# Power_24Vto160V.net
KiCad netlist of a schematic drawn in Altium Designer
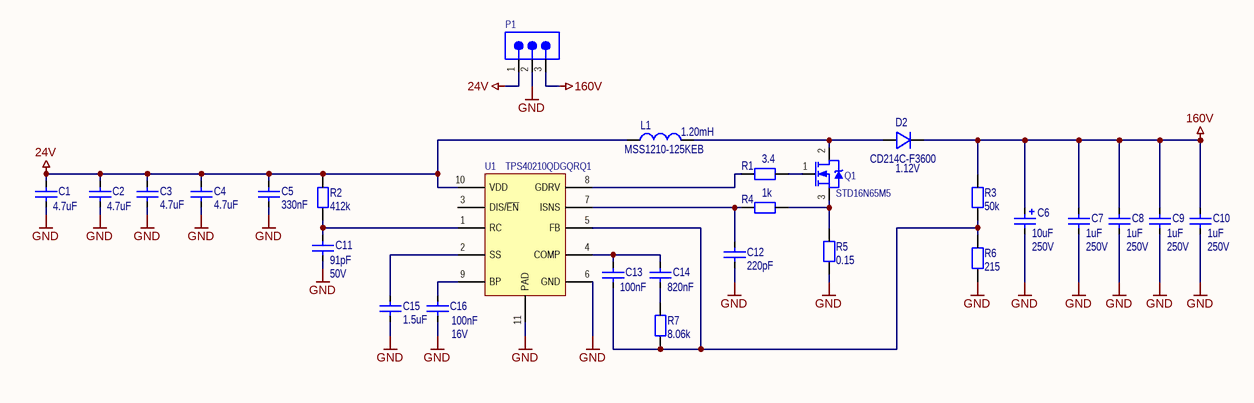
[diagram p0: Power_24Vto160V.SchDoc]

(export (version "E")
  (design (tool "Eeschema 10.0.6"))
  (components
    (comp (ref "C1")
      (value "4.7uF")
      (footprint "1210_C")
      (description "GRM32ER71H475KA88L")
      (fields (field (name "TOLERANCE") "±10%") (field (name "MANUFACTURER") "muRata"))
      (libsource (lib "Nixie") (part "GRM32ER71H475KA88L"))
    )
    (comp (ref "C2")
      (value "4.7uF")
      (footprint "1210_C")
      (description "GRM32ER71H475KA88L")
      (fields (field (name "TOLERANCE") "±10%") (field (name "MANUFACTURER") "muRata"))
      (libsource (lib "Nixie") (part "GRM32ER71H475KA88L"))
    )
    (comp (ref "C3")
      (value "4.7uF")
      (footprint "1210_C")
      (description "GRM32ER71H475KA88L")
      (fields (field (name "TOLERANCE") "±10%") (field (name "MANUFACTURER") "muRata"))
      (libsource (lib "Nixie") (part "GRM32ER71H475KA88L"))
    )
    (comp (ref "C4")
      (value "4.7uF")
      (footprint "1210_C")
      (description "GRM32ER71H475KA88L")
      (fields (field (name "TOLERANCE") "±10%") (field (name "MANUFACTURER") "muRata"))
      (libsource (lib "Nixie") (part "GRM32ER71H475KA88L"))
    )
    (comp (ref "C5")
      (value "330nF")
      (footprint "0603_C")
      (description "C1608X5R1H334K080AB")
      (fields (field (name "TOLERANCE") "±10%") (field (name "MANUFACTURER") "TDK"))
      (libsource (lib "Nixie") (part "C1608X5R1H334K080AB"))
    )
    (comp (ref "C6")
      (value "10uF")
      (footprint "CAPAE109103X100M")
      (description "UUX2E100MNL1GS")
      (fields
        (field (name "TOLERANCE") "±20%")
        (field (name "MANUFACTURER") "Nichicon")
        (field (name "VOLTAGE_RATING") "250V")
      )
      (libsource (lib "Nixie") (part "UUX2E100MNL1GS"))
    )
    (comp (ref "C7")
      (value "1uF")
      (footprint "CAPC5750X27_EIA-2220")
      (description "GRM55DR72E105KW01L")
      (fields
        (field (name "TOLERANCE") "±10%")
        (field (name "VOLTAGE_RATING") "250V")
        (field (name "MANUFACTURER") "muRata")
      )
      (libsource (lib "Nixie") (part "GRM55DR72E105KW01L"))
    )
    (comp (ref "C8")
      (value "1uF")
      (footprint "CAPC5750X27_EIA-2220")
      (description "GRM55DR72E105KW01L")
      (fields
        (field (name "TOLERANCE") "±10%")
        (field (name "VOLTAGE_RATING") "250V")
        (field (name "MANUFACTURER") "muRata")
      )
      (libsource (lib "Nixie") (part "GRM55DR72E105KW01L"))
    )
    (comp (ref "C9")
      (value "1uF")
      (footprint "CAPC5750X27_EIA-2220")
      (description "GRM55DR72E105KW01L")
      (fields
        (field (name "TOLERANCE") "±10%")
        (field (name "VOLTAGE_RATING") "250V")
        (field (name "MANUFACTURER") "muRata")
      )
      (libsource (lib "Nixie") (part "GRM55DR72E105KW01L"))
    )
    (comp (ref "C10")
      (value "1uF")
      (footprint "CAPC5750X27_EIA-2220")
      (description "GRM55DR72E105KW01L")
      (fields
        (field (name "TOLERANCE") "±10%")
        (field (name "VOLTAGE_RATING") "250V")
        (field (name "MANUFACTURER") "muRata")
      )
      (libsource (lib "Nixie") (part "GRM55DR72E105KW01L"))
    )
    (comp (ref "C11")
      (value "91pF")
      (footprint "0603_C")
      (description "GRM1885C1H910JA01D")
      (fields
        (field (name "TOLERANCE") "±10%")
        (field (name "VOLTAGE_RATING") "50V")
        (field (name "MANUFACTURER") "muRata")
      )
      (libsource (lib "Nixie") (part "GRM1885C1H910JA01D"))
    )
    (comp (ref "C12")
      (value "220pF")
      (footprint "CAPC2012X12_EIA-0805")
      (description "CC0805JRNPO9BN221")
      (fields (field (name "TOLERANCE") "±10%") (field (name "MANUFACTURER") "Yageo"))
      (libsource (lib "Nixie") (part "CC0805JRNPO9BN221"))
    )
    (comp (ref "C13")
      (value "100nF")
      (footprint "CAPC2012X12_EIA-0805")
      (description "CC0805KRX7R8BB104")
      (fields (field (name "TOLERANCE") "±10%") (field (name "MANUFACTURER") "Yageo"))
      (libsource (lib "Nixie") (part "CC0805KRX7R8BB104"))
    )
    (comp (ref "C14")
      (value "820nF")
      (footprint "CAPC1005X05_EIA-0402")
      (description "GRM155R61A824KE15D")
      (fields (field (name "TOLERANCE") "±10%") (field (name "MANUFACTURER") "muRata"))
      (libsource (lib "Nixie") (part "GRM155R61A824KE15D"))
    )
    (comp (ref "C15")
      (value "1.5uF")
      (footprint "0603_C")
      (description "C1608X7R1A155K080AC")
      (fields (field (name "TOLERANCE") "±10%") (field (name "MANUFACTURER") "TDK"))
      (libsource (lib "Nixie") (part "C1608X7R1A155K080AC"))
    )
    (comp (ref "C16")
      (value "100nF")
      (footprint "0603_C")
      (description "EMK107B7105KA-T")
      (fields
        (field (name "TOLERANCE") "±10%")
        (field (name "VOLTAGE_RATING") "16V")
        (field (name "MANUFACTURER") "Taiyo Yuden")
      )
      (libsource (lib "Nixie") (part "EMK107B7105KA-T"))
    )
    (comp (ref "D2")
      (value "CD214C-F3600")
      (footprint "DIOM6959X26N")
      (description "600V, 3amp")
      (fields (field (name "VOLTAGE") "1.12V"))
      (libsource (lib "Nixie") (part "CD214C-F3600"))
    )
    (comp (ref "L1")
      (value "1.20mH")
      (footprint "IND_COILCRAFT_MSS1260")
      (description "Inductor")
      (fields (field (name "ORDERNUMBER") "MSS1210-125KEB"))
      (libsource (lib "Nixie") (part "MSS1210-125KEB"))
    )
    (comp (ref "P1")
      (value "power")
      (footprint "MOLEX_22-28-4030")
      (description "Header single row 1x3pin")
      (fields
        (field (name "PART_NUMBER") "1007795")
        (field (name "MANUFACTURER") "molex")
        (field (name "CHECK_STATE") "2014-07-24_DW_MJ")
      )
      (libsource (lib "PCB") (part "M_1x3PIN-molex"))
    )
    (comp (ref "Q1")
      (value "STD16N65M5")
      (footprint "DPAK228P972X240-3N")
      (description "N-channel MOSFET 650V")
      (fields (field (name "ORDER_NUMBER") "STD16N65M5"))
      (libsource (lib "Nixie") (part "STD16N65M5"))
    )
    (comp (ref "R1")
      (value "3.4")
      (footprint "0603_R")
      (description "CRCW06033R40FKEA")
      (fields (field (name "PART_NUMBER") "1347890") (field (name "TOLERANCE") "1%"))
      (libsource (lib "Nixie") (part "CRCW06033R40FKEA"))
    )
    (comp (ref "R2")
      (value "412k")
      (footprint "0603_R")
      (description "ERJ-3EKF4123V")
      (fields (field (name "PART_NUMBER") "1347890") (field (name "TOLERANCE") "1%"))
      (libsource (lib "Nixie") (part "R_ERJ-3EKF4123V"))
    )
    (comp (ref "R3")
      (value "50k")
      (footprint "RESC3216X06_EIA-1206")
      (description "PNM1206E5002BST1")
      (fields (field (name "PART_NUMBER") "1347890") (field (name "TOLERANCE") "0.1%"))
      (libsource (lib "Nixie") (part "PNM1206E5002BST1"))
    )
    (comp (ref "R4")
      (value "1k")
      (footprint "0603_R")
      (description "CRCW02011K00FKED")
      (fields (field (name "PART_NUMBER") "1347890") (field (name "TOLERANCE") "1%"))
      (libsource (lib "Nixie") (part "CRCW02011K00FKED"))
    )
    (comp (ref "R5")
      (value "0.15")
      (footprint "0603_R")
      (description "ERJ-3RSFR15V")
      (fields (field (name "TOLERANCE") "1%") (field (name "MANUFACTURER") "Panasonic"))
      (libsource (lib "Nixie") (part "ERJ-3RSFR15V"))
    )
    (comp (ref "R6")
      (value "215")
      (footprint "0603_R")
      (description "ERJ-3EKF2150V")
      (fields (field (name "TOLERANCE") "1%") (field (name "MANUFACTURER") "Panasonic"))
      (libsource (lib "Nixie") (part "ERJ-3EKF2150V"))
    )
    (comp (ref "R7")
      (value "8.06k")
      (footprint "0603_R")
      (description "CRCW06038K06FKEA")
      (fields (field (name "PART_NUMBER") "1347890") (field (name "TOLERANCE") "1%"))
      (libsource (lib "Nixie") (part "R_CRCW06038K06FKEA"))
    )
    (comp (ref "U1")
      (value "TPS40210QDGQRQ1")
      (footprint "TSSOP50P490X110_HS-11N")
      (fields (field (name "MANUFACTURER") "TI") (field (name "ORDER_NUMBER") "TPS40210QDGQRQ1"))
      (libsource (lib "Nixie") (part "TPS40210-Q1"))
    )
  )
  (nets
    (net (code "1") (name "24V") (class "Default")
      (node (ref "C1") (pin "2") (pinfunction "2_2") (pintype "passive"))
      (node (ref "C2") (pin "2") (pinfunction "2_2") (pintype "passive"))
      (node (ref "C3") (pin "2") (pinfunction "2_2") (pintype "passive"))
      (node (ref "C4") (pin "2") (pinfunction "2_2") (pintype "passive"))
      (node (ref "C5") (pin "2") (pinfunction "2_2") (pintype "passive"))
      (node (ref "L1") (pin "1") (pinfunction "1_1") (pintype "passive"))
      (node (ref "P1") (pin "1") (pinfunction "1_1") (pintype "passive"))
      (node (ref "R2") (pin "2") (pinfunction "2_2") (pintype "passive"))
      (node (ref "U1") (pin "10") (pinfunction "VDD_10") (pintype "power_in"))
    )
    (net (code "2") (name "160V") (class "Default")
      (node (ref "C10") (pin "2") (pinfunction "2_2") (pintype "passive"))
      (node (ref "C6") (pin "1") (pinfunction "1_1") (pintype "passive"))
      (node (ref "C7") (pin "2") (pinfunction "2_2") (pintype "passive"))
      (node (ref "C8") (pin "2") (pinfunction "2_2") (pintype "passive"))
      (node (ref "C9") (pin "2") (pinfunction "2_2") (pintype "passive"))
      (node (ref "D2") (pin "1") (pinfunction "K_1") (pintype "passive"))
      (node (ref "P1") (pin "3") (pinfunction "3_3") (pintype "passive"))
      (node (ref "R3") (pin "2") (pinfunction "2_2") (pintype "passive"))
    )
    (net (code "3") (name "GND") (class "Default")
      (node (ref "C1") (pin "1") (pinfunction "1_1") (pintype "passive"))
      (node (ref "C10") (pin "1") (pinfunction "1_1") (pintype "passive"))
      (node (ref "C11") (pin "1") (pinfunction "1_1") (pintype "passive"))
      (node (ref "C12") (pin "1") (pinfunction "1_1") (pintype "passive"))
      (node (ref "C15") (pin "1") (pinfunction "1_1") (pintype "passive"))
      (node (ref "C16") (pin "1") (pinfunction "1_1") (pintype "passive"))
      (node (ref "C2") (pin "1") (pinfunction "1_1") (pintype "passive"))
      (node (ref "C3") (pin "1") (pinfunction "1_1") (pintype "passive"))
      (node (ref "C4") (pin "1") (pinfunction "1_1") (pintype "passive"))
      (node (ref "C5") (pin "1") (pinfunction "1_1") (pintype "passive"))
      (node (ref "C6") (pin "2") (pinfunction "2_2") (pintype "passive"))
      (node (ref "C7") (pin "1") (pinfunction "1_1") (pintype "passive"))
      (node (ref "C8") (pin "1") (pinfunction "1_1") (pintype "passive"))
      (node (ref "C9") (pin "1") (pinfunction "1_1") (pintype "passive"))
      (node (ref "P1") (pin "2") (pinfunction "2_2") (pintype "passive"))
      (node (ref "R5") (pin "1") (pinfunction "1_1") (pintype "passive"))
      (node (ref "R6") (pin "1") (pinfunction "1_1") (pintype "passive"))
      (node (ref "U1") (pin "11") (pinfunction "PAD_11") (pintype "power_in"))
      (node (ref "U1") (pin "6") (pinfunction "GND_6") (pintype "power_in"))
    )
    (net (code "4") (name "Net-(C14-Pad1)") (class "Default")
      (node (ref "C14") (pin "1") (pinfunction "1_1") (pintype "passive"))
      (node (ref "R7") (pin "2") (pinfunction "2_2") (pintype "passive"))
    )
    (net (code "5") (name "Net-(D2-A)") (class "Default")
      (node (ref "D2") (pin "2") (pinfunction "A_2") (pintype "passive"))
      (node (ref "L1") (pin "2") (pinfunction "2_2") (pintype "passive"))
      (node (ref "Q1") (pin "2") (pinfunction "D_2") (pintype "passive"))
    )
    (net (code "6") (name "Net-(Q1-G)") (class "Default")
      (node (ref "Q1") (pin "1") (pinfunction "G_1") (pintype "passive"))
      (node (ref "R1") (pin "2") (pinfunction "2_2") (pintype "passive"))
    )
    (net (code "7") (name "Net-(Q1-S)") (class "Default")
      (node (ref "Q1") (pin "3") (pinfunction "S_3") (pintype "passive"))
      (node (ref "R4") (pin "2") (pinfunction "2_2") (pintype "passive"))
      (node (ref "R5") (pin "2") (pinfunction "2_2") (pintype "passive"))
    )
    (net (code "8") (name "Net-(U1-BP)") (class "Default")
      (node (ref "C16") (pin "2") (pinfunction "2_2") (pintype "passive"))
      (node (ref "U1") (pin "9") (pinfunction "BP_9") (pintype "power_in"))
    )
    (net (code "9") (name "Net-(U1-COMP)") (class "Default")
      (node (ref "C13") (pin "2") (pinfunction "2_2") (pintype "passive"))
      (node (ref "C14") (pin "2") (pinfunction "2_2") (pintype "passive"))
      (node (ref "U1") (pin "4") (pinfunction "COMP_4") (pintype "power_in"))
    )
    (net (code "10") (name "Net-(U1-FB)") (class "Default")
      (node (ref "C13") (pin "1") (pinfunction "1_1") (pintype "passive"))
      (node (ref "R3") (pin "1") (pinfunction "1_1") (pintype "passive"))
      (node (ref "R6") (pin "2") (pinfunction "2_2") (pintype "passive"))
      (node (ref "R7") (pin "1") (pinfunction "1_1") (pintype "passive"))
      (node (ref "U1") (pin "5") (pinfunction "FB_5") (pintype "power_in"))
    )
    (net (code "11") (name "Net-(U1-GDRV)") (class "Default")
      (node (ref "R1") (pin "1") (pinfunction "1_1") (pintype "passive"))
      (node (ref "U1") (pin "8") (pinfunction "GDRV_8") (pintype "power_in"))
    )
    (net (code "12") (name "Net-(U1-ISNS)") (class "Default")
      (node (ref "C12") (pin "2") (pinfunction "2_2") (pintype "passive"))
      (node (ref "R4") (pin "1") (pinfunction "1_1") (pintype "passive"))
      (node (ref "U1") (pin "7") (pinfunction "ISNS_7") (pintype "power_in"))
    )
    (net (code "13") (name "Net-(U1-RC)") (class "Default")
      (node (ref "C11") (pin "2") (pinfunction "2_2") (pintype "passive"))
      (node (ref "R2") (pin "1") (pinfunction "1_1") (pintype "passive"))
      (node (ref "U1") (pin "1") (pinfunction "RC_1") (pintype "power_in"))
    )
    (net (code "14") (name "Net-(U1-SS)") (class "Default")
      (node (ref "C15") (pin "2") (pinfunction "2_2") (pintype "passive"))
      (node (ref "U1") (pin "2") (pinfunction "SS_2") (pintype "power_in"))
    )
    (net (code "15") (name "unconnected-(U1-DIS{slash}~{EN}-Pad3)") (class "Default")
      (node (ref "U1") (pin "3") (pinfunction "DIS/~{EN}_3") (pintype "power_in"))
    )
  )
)
